# DE-010824_02.net
KiCad netlist of a schematic drawn in Altium Designer
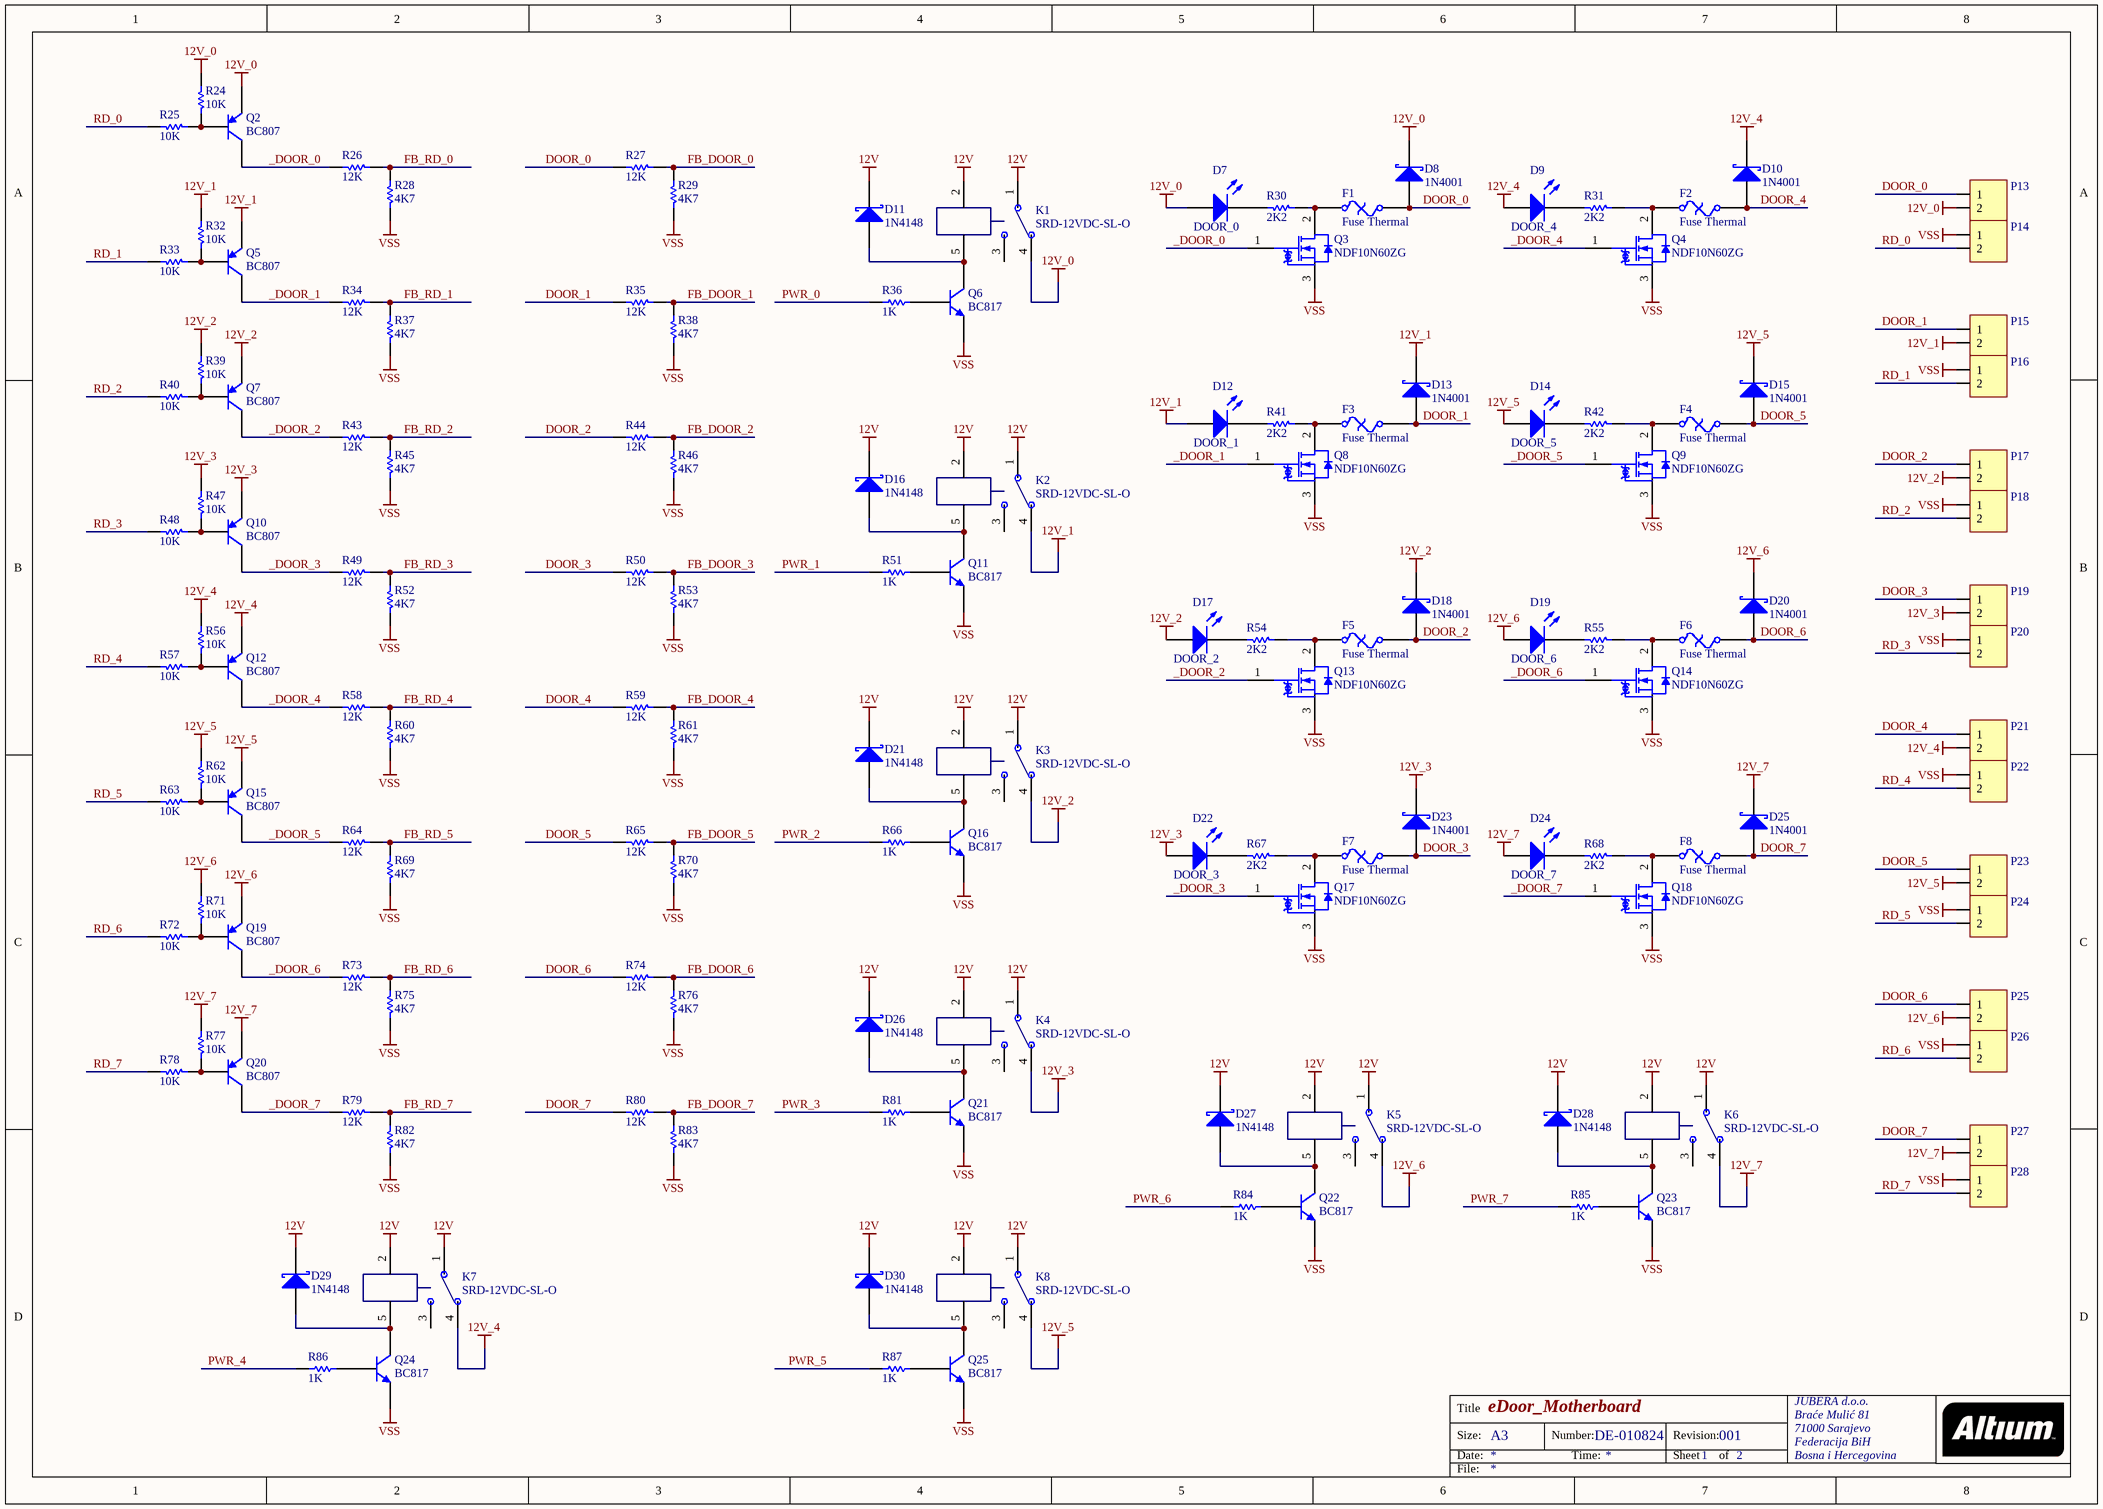
[diagram p0: DE-010824_02.SchDoc]

(export (version "E")
  (design (tool "Eeschema 10.0.6"))
  (components
    (comp (ref "D7")
      (value "DOOR_0")
      (footprint "1.6X0.8X0.8")
      (description "Blue Surface Mount Chip LED, Blue")
      (libsource (lib "DE-010824") (part "HSMB-C190"))
    )
    (comp (ref "D8")
      (value "1N4001")
      (footprint "SMB")
      (description "Schottky Diode")
      (libsource (lib "DE-010824") (part "D Schottky"))
    )
    (comp (ref "D9")
      (value "DOOR_4")
      (footprint "1.6X0.8X0.8")
      (description "Blue Surface Mount Chip LED, Blue")
      (libsource (lib "DE-010824") (part "HSMB-C190"))
    )
    (comp (ref "D10")
      (value "1N4001")
      (footprint "SMB")
      (description "Schottky Diode")
      (libsource (lib "DE-010824") (part "D Schottky"))
    )
    (comp (ref "D11")
      (value "1N4148")
      (footprint "SOD323")
      (description "Schottky Barrier Diode")
      (libsource (lib "DE-010824") (part "1PS76SB10"))
    )
    (comp (ref "D12")
      (value "DOOR_1")
      (footprint "1.6X0.8X0.8")
      (description "Blue Surface Mount Chip LED, Blue")
      (libsource (lib "DE-010824") (part "HSMB-C190"))
    )
    (comp (ref "D13")
      (value "1N4001")
      (footprint "SMB")
      (description "Schottky Diode")
      (libsource (lib "DE-010824") (part "D Schottky"))
    )
    (comp (ref "D14")
      (value "DOOR_5")
      (footprint "1.6X0.8X0.8")
      (description "Blue Surface Mount Chip LED, Blue")
      (libsource (lib "DE-010824") (part "HSMB-C190"))
    )
    (comp (ref "D15")
      (value "1N4001")
      (footprint "SMB")
      (description "Schottky Diode")
      (libsource (lib "DE-010824") (part "D Schottky"))
    )
    (comp (ref "D16")
      (value "1N4148")
      (footprint "SOD323")
      (description "Schottky Barrier Diode")
      (libsource (lib "DE-010824") (part "1PS76SB10"))
    )
    (comp (ref "D17")
      (value "DOOR_2")
      (footprint "1.6X0.8X0.8")
      (description "Blue Surface Mount Chip LED, Blue")
      (libsource (lib "DE-010824") (part "HSMB-C190"))
    )
    (comp (ref "D18")
      (value "1N4001")
      (footprint "SMB")
      (description "Schottky Diode")
      (libsource (lib "DE-010824") (part "D Schottky"))
    )
    (comp (ref "D19")
      (value "DOOR_6")
      (footprint "1.6X0.8X0.8")
      (description "Blue Surface Mount Chip LED, Blue")
      (libsource (lib "DE-010824") (part "HSMB-C190"))
    )
    (comp (ref "D20")
      (value "1N4001")
      (footprint "SMB")
      (description "Schottky Diode")
      (libsource (lib "DE-010824") (part "D Schottky"))
    )
    (comp (ref "D21")
      (value "1N4148")
      (footprint "SOD323")
      (description "Schottky Barrier Diode")
      (libsource (lib "DE-010824") (part "1PS76SB10"))
    )
    (comp (ref "D22")
      (value "DOOR_3")
      (footprint "1.6X0.8X0.8")
      (description "Blue Surface Mount Chip LED, Blue")
      (libsource (lib "DE-010824") (part "HSMB-C190"))
    )
    (comp (ref "D23")
      (value "1N4001")
      (footprint "SMB")
      (description "Schottky Diode")
      (libsource (lib "DE-010824") (part "D Schottky"))
    )
    (comp (ref "D24")
      (value "DOOR_7")
      (footprint "1.6X0.8X0.8")
      (description "Blue Surface Mount Chip LED, Blue")
      (libsource (lib "DE-010824") (part "HSMB-C190"))
    )
    (comp (ref "D25")
      (value "1N4001")
      (footprint "SMB")
      (description "Schottky Diode")
      (libsource (lib "DE-010824") (part "D Schottky"))
    )
    (comp (ref "D26")
      (value "1N4148")
      (footprint "SOD323")
      (description "Schottky Barrier Diode")
      (libsource (lib "DE-010824") (part "1PS76SB10"))
    )
    (comp (ref "D27")
      (value "1N4148")
      (footprint "SOD323")
      (description "Schottky Barrier Diode")
      (libsource (lib "DE-010824") (part "1PS76SB10"))
    )
    (comp (ref "D28")
      (value "1N4148")
      (footprint "SOD323")
      (description "Schottky Barrier Diode")
      (libsource (lib "DE-010824") (part "1PS76SB10"))
    )
    (comp (ref "D29")
      (value "1N4148")
      (footprint "SOD323")
      (description "Schottky Barrier Diode")
      (libsource (lib "DE-010824") (part "1PS76SB10"))
    )
    (comp (ref "D30")
      (value "1N4148")
      (footprint "SOD323")
      (description "Schottky Barrier Diode")
      (libsource (lib "DE-010824") (part "1PS76SB10"))
    )
    (comp (ref "F1")
      (value "Fuse Thermal")
      (footprint "PIN-W2/E2.8")
      (description "Thermal Fuse")
      (libsource (lib "Miscellaneous Devices") (part "Fuse Thermal"))
    )
    (comp (ref "F2")
      (value "Fuse Thermal")
      (footprint "PIN-W2/E2.8")
      (description "Thermal Fuse")
      (libsource (lib "Miscellaneous Devices") (part "Fuse Thermal"))
    )
    (comp (ref "F3")
      (value "Fuse Thermal")
      (footprint "PIN-W2/E2.8")
      (description "Thermal Fuse")
      (libsource (lib "Miscellaneous Devices") (part "Fuse Thermal"))
    )
    (comp (ref "F4")
      (value "Fuse Thermal")
      (footprint "PIN-W2/E2.8")
      (description "Thermal Fuse")
      (libsource (lib "Miscellaneous Devices") (part "Fuse Thermal"))
    )
    (comp (ref "F5")
      (value "Fuse Thermal")
      (footprint "PIN-W2/E2.8")
      (description "Thermal Fuse")
      (libsource (lib "Miscellaneous Devices") (part "Fuse Thermal"))
    )
    (comp (ref "F6")
      (value "Fuse Thermal")
      (footprint "PIN-W2/E2.8")
      (description "Thermal Fuse")
      (libsource (lib "Miscellaneous Devices") (part "Fuse Thermal"))
    )
    (comp (ref "F7")
      (value "Fuse Thermal")
      (footprint "PIN-W2/E2.8")
      (description "Thermal Fuse")
      (libsource (lib "Miscellaneous Devices") (part "Fuse Thermal"))
    )
    (comp (ref "F8")
      (value "Fuse Thermal")
      (footprint "PIN-W2/E2.8")
      (description "Thermal Fuse")
      (libsource (lib "Miscellaneous Devices") (part "Fuse Thermal"))
    )
    (comp (ref "K1")
      (value "SRD-12VDC-SL-O")
      (footprint "SRD-12VDC-SL-O")
      (description "SPDT PCB relay 12Vc coil")
      (libsource (lib "DE-010824") (part "SRD-12VDC-SL-O"))
    )
    (comp (ref "K2")
      (value "SRD-12VDC-SL-O")
      (footprint "SRD-12VDC-SL-O")
      (description "SPDT PCB relay 12Vc coil")
      (libsource (lib "DE-010824") (part "SRD-12VDC-SL-O"))
    )
    (comp (ref "K3")
      (value "SRD-12VDC-SL-O")
      (footprint "SRD-12VDC-SL-O")
      (description "SPDT PCB relay 12Vc coil")
      (libsource (lib "DE-010824") (part "SRD-12VDC-SL-O"))
    )
    (comp (ref "K4")
      (value "SRD-12VDC-SL-O")
      (footprint "SRD-12VDC-SL-O")
      (description "SPDT PCB relay 12Vc coil")
      (libsource (lib "DE-010824") (part "SRD-12VDC-SL-O"))
    )
    (comp (ref "K5")
      (value "SRD-12VDC-SL-O")
      (footprint "SRD-12VDC-SL-O")
      (description "SPDT PCB relay 12Vc coil")
      (libsource (lib "DE-010824") (part "SRD-12VDC-SL-O"))
    )
    (comp (ref "K6")
      (value "SRD-12VDC-SL-O")
      (footprint "SRD-12VDC-SL-O")
      (description "SPDT PCB relay 12Vc coil")
      (libsource (lib "DE-010824") (part "SRD-12VDC-SL-O"))
    )
    (comp (ref "K7")
      (value "SRD-12VDC-SL-O")
      (footprint "SRD-12VDC-SL-O")
      (description "SPDT PCB relay 12Vc coil")
      (libsource (lib "DE-010824") (part "SRD-12VDC-SL-O"))
    )
    (comp (ref "K8")
      (value "SRD-12VDC-SL-O")
      (footprint "SRD-12VDC-SL-O")
      (description "SPDT PCB relay 12Vc coil")
      (libsource (lib "DE-010824") (part "SRD-12VDC-SL-O"))
    )
    (comp (ref "P13")
      (value "DOOR_0")
      (footprint "TERMINAL BLOK 2")
      (description "Terminal blok konektor 3,5 mm")
      (libsource (lib "DE-010824") (part "TERMINAL BLOK 2"))
    )
    (comp (ref "P14")
      (value "GND")
      (footprint "TERMINAL BLOK 2")
      (description "Terminal blok konektor 3,5 mm")
      (libsource (lib "DE-010824") (part "TERMINAL BLOK 2"))
    )
    (comp (ref "P15")
      (value "DOOR_0")
      (footprint "TERMINAL BLOK 2")
      (description "Terminal blok konektor 3,5 mm")
      (libsource (lib "DE-010824") (part "TERMINAL BLOK 2"))
    )
    (comp (ref "P16")
      (value "GND")
      (footprint "TERMINAL BLOK 2")
      (description "Terminal blok konektor 3,5 mm")
      (libsource (lib "DE-010824") (part "TERMINAL BLOK 2"))
    )
    (comp (ref "P17")
      (value "DOOR_0")
      (footprint "TERMINAL BLOK 2")
      (description "Terminal blok konektor 3,5 mm")
      (libsource (lib "DE-010824") (part "TERMINAL BLOK 2"))
    )
    (comp (ref "P18")
      (value "GND")
      (footprint "TERMINAL BLOK 2")
      (description "Terminal blok konektor 3,5 mm")
      (libsource (lib "DE-010824") (part "TERMINAL BLOK 2"))
    )
    (comp (ref "P19")
      (value "DOOR_0")
      (footprint "TERMINAL BLOK 2")
      (description "Terminal blok konektor 3,5 mm")
      (libsource (lib "DE-010824") (part "TERMINAL BLOK 2"))
    )
    (comp (ref "P20")
      (value "GND")
      (footprint "TERMINAL BLOK 2")
      (description "Terminal blok konektor 3,5 mm")
      (libsource (lib "DE-010824") (part "TERMINAL BLOK 2"))
    )
    (comp (ref "P21")
      (value "DOOR_0")
      (footprint "TERMINAL BLOK 2")
      (description "Terminal blok konektor 3,5 mm")
      (libsource (lib "DE-010824") (part "TERMINAL BLOK 2"))
    )
    (comp (ref "P22")
      (value "GND")
      (footprint "TERMINAL BLOK 2")
      (description "Terminal blok konektor 3,5 mm")
      (libsource (lib "DE-010824") (part "TERMINAL BLOK 2"))
    )
    (comp (ref "P23")
      (value "DOOR_0")
      (footprint "TERMINAL BLOK 2")
      (description "Terminal blok konektor 3,5 mm")
      (libsource (lib "DE-010824") (part "TERMINAL BLOK 2"))
    )
    (comp (ref "P24")
      (value "GND")
      (footprint "TERMINAL BLOK 2")
      (description "Terminal blok konektor 3,5 mm")
      (libsource (lib "DE-010824") (part "TERMINAL BLOK 2"))
    )
    (comp (ref "P25")
      (value "DOOR_0")
      (footprint "TERMINAL BLOK 2")
      (description "Terminal blok konektor 3,5 mm")
      (libsource (lib "DE-010824") (part "TERMINAL BLOK 2"))
    )
    (comp (ref "P26")
      (value "GND")
      (footprint "TERMINAL BLOK 2")
      (description "Terminal blok konektor 3,5 mm")
      (libsource (lib "DE-010824") (part "TERMINAL BLOK 2"))
    )
    (comp (ref "P27")
      (value "DOOR_0")
      (footprint "TERMINAL BLOK 2")
      (description "Terminal blok konektor 3,5 mm")
      (libsource (lib "DE-010824") (part "TERMINAL BLOK 2"))
    )
    (comp (ref "P28")
      (value "GND")
      (footprint "TERMINAL BLOK 2")
      (description "Terminal blok konektor 3,5 mm")
      (libsource (lib "DE-010824") (part "TERMINAL BLOK 2"))
    )
    (comp (ref "Q2")
      (value "BC807")
      (footprint "SOT23_N")
      (description "PNP General-purpose Transistor")
      (libsource (lib "DE-010824") (part "BC807"))
    )
    (comp (ref "Q3")
      (value "NDF10N60ZG")
      (footprint "ONSC-TO-220-3-221D-03")
      (description "N-Channel Power MOSFET 600 V, 0.75 Ohm, 3-Pin TO-220, Pb-Free, Tube")
      (fields (field (name "MANUFACTURER") "On Semiconductor"))
      (libsource (lib "ON Semi MOSFETs") (part "NDF10N60ZG"))
    )
    (comp (ref "Q4")
      (value "NDF10N60ZG")
      (footprint "ONSC-TO-220-3-221D-03")
      (description "N-Channel Power MOSFET 600 V, 0.75 Ohm, 3-Pin TO-220, Pb-Free, Tube")
      (fields (field (name "MANUFACTURER") "On Semiconductor"))
      (libsource (lib "ON Semi MOSFETs") (part "NDF10N60ZG"))
    )
    (comp (ref "Q5")
      (value "BC807")
      (footprint "SOT23_N")
      (description "PNP General-purpose Transistor")
      (libsource (lib "DE-010824") (part "BC807"))
    )
    (comp (ref "Q6")
      (value "BC817")
      (footprint "SOT23_N")
      (description "NPN General-purpose Transistor")
      (libsource (lib "DE-010824") (part "BC817"))
    )
    (comp (ref "Q7")
      (value "BC807")
      (footprint "SOT23_N")
      (description "PNP General-purpose Transistor")
      (libsource (lib "DE-010824") (part "BC807"))
    )
    (comp (ref "Q8")
      (value "NDF10N60ZG")
      (footprint "ONSC-TO-220-3-221D-03")
      (description "N-Channel Power MOSFET 600 V, 0.75 Ohm, 3-Pin TO-220, Pb-Free, Tube")
      (fields (field (name "MANUFACTURER") "On Semiconductor"))
      (libsource (lib "ON Semi MOSFETs") (part "NDF10N60ZG"))
    )
    (comp (ref "Q9")
      (value "NDF10N60ZG")
      (footprint "ONSC-TO-220-3-221D-03")
      (description "N-Channel Power MOSFET 600 V, 0.75 Ohm, 3-Pin TO-220, Pb-Free, Tube")
      (fields (field (name "MANUFACTURER") "On Semiconductor"))
      (libsource (lib "ON Semi MOSFETs") (part "NDF10N60ZG"))
    )
    (comp (ref "Q10")
      (value "BC807")
      (footprint "SOT23_N")
      (description "PNP General-purpose Transistor")
      (libsource (lib "DE-010824") (part "BC807"))
    )
    (comp (ref "Q11")
      (value "BC817")
      (footprint "SOT23_N")
      (description "NPN General-purpose Transistor")
      (libsource (lib "DE-010824") (part "BC817"))
    )
    (comp (ref "Q12")
      (value "BC807")
      (footprint "SOT23_N")
      (description "PNP General-purpose Transistor")
      (libsource (lib "DE-010824") (part "BC807"))
    )
    (comp (ref "Q13")
      (value "NDF10N60ZG")
      (footprint "ONSC-TO-220-3-221D-03")
      (description "N-Channel Power MOSFET 600 V, 0.75 Ohm, 3-Pin TO-220, Pb-Free, Tube")
      (fields (field (name "MANUFACTURER") "On Semiconductor"))
      (libsource (lib "ON Semi MOSFETs") (part "NDF10N60ZG"))
    )
    (comp (ref "Q14")
      (value "NDF10N60ZG")
      (footprint "ONSC-TO-220-3-221D-03")
      (description "N-Channel Power MOSFET 600 V, 0.75 Ohm, 3-Pin TO-220, Pb-Free, Tube")
      (fields (field (name "MANUFACTURER") "On Semiconductor"))
      (libsource (lib "ON Semi MOSFETs") (part "NDF10N60ZG"))
    )
    (comp (ref "Q15")
      (value "BC807")
      (footprint "SOT23_N")
      (description "PNP General-purpose Transistor")
      (libsource (lib "DE-010824") (part "BC807"))
    )
    (comp (ref "Q16")
      (value "BC817")
      (footprint "SOT23_N")
      (description "NPN General-purpose Transistor")
      (libsource (lib "DE-010824") (part "BC817"))
    )
    (comp (ref "Q17")
      (value "NDF10N60ZG")
      (footprint "ONSC-TO-220-3-221D-03")
      (description "N-Channel Power MOSFET 600 V, 0.75 Ohm, 3-Pin TO-220, Pb-Free, Tube")
      (fields (field (name "MANUFACTURER") "On Semiconductor"))
      (libsource (lib "ON Semi MOSFETs") (part "NDF10N60ZG"))
    )
    (comp (ref "Q18")
      (value "NDF10N60ZG")
      (footprint "ONSC-TO-220-3-221D-03")
      (description "N-Channel Power MOSFET 600 V, 0.75 Ohm, 3-Pin TO-220, Pb-Free, Tube")
      (fields (field (name "MANUFACTURER") "On Semiconductor"))
      (libsource (lib "ON Semi MOSFETs") (part "NDF10N60ZG"))
    )
    (comp (ref "Q19")
      (value "BC807")
      (footprint "SOT23_N")
      (description "PNP General-purpose Transistor")
      (libsource (lib "DE-010824") (part "BC807"))
    )
    (comp (ref "Q20")
      (value "BC807")
      (footprint "SOT23_N")
      (description "PNP General-purpose Transistor")
      (libsource (lib "DE-010824") (part "BC807"))
    )
    (comp (ref "Q21")
      (value "BC817")
      (footprint "SOT23_N")
      (description "NPN General-purpose Transistor")
      (libsource (lib "DE-010824") (part "BC817"))
    )
    (comp (ref "Q22")
      (value "BC817")
      (footprint "SOT23_N")
      (description "NPN General-purpose Transistor")
      (libsource (lib "DE-010824") (part "BC817"))
    )
    (comp (ref "Q23")
      (value "BC817")
      (footprint "SOT23_N")
      (description "NPN General-purpose Transistor")
      (libsource (lib "DE-010824") (part "BC817"))
    )
    (comp (ref "Q24")
      (value "BC817")
      (footprint "SOT23_N")
      (description "NPN General-purpose Transistor")
      (libsource (lib "DE-010824") (part "BC817"))
    )
    (comp (ref "Q25")
      (value "BC817")
      (footprint "SOT23_N")
      (description "NPN General-purpose Transistor")
      (libsource (lib "DE-010824") (part "BC817"))
    )
    (comp (ref "R24") (value "10K") (footprint "ERA-0603") (libsource (lib "DE-220817") (part "ERAV")))
    (comp (ref "R25") (value "10K") (footprint "ERA-0603") (libsource (lib "DE-220817") (part "ERAV")))
    (comp (ref "R26") (value "12K") (footprint "ERA-0603") (libsource (lib "DE-220817") (part "ERAV")))
    (comp (ref "R27") (value "12K") (footprint "ERA-0603") (libsource (lib "DE-220817") (part "ERAV")))
    (comp (ref "R28") (value "4K7") (footprint "ERA-0603") (libsource (lib "DE-220817") (part "ERAV")))
    (comp (ref "R29") (value "4K7") (footprint "ERA-0603") (libsource (lib "DE-220817") (part "ERAV")))
    (comp (ref "R30") (value "2K2") (footprint "ERA-0603") (libsource (lib "DE-220817") (part "ERAV")))
    (comp (ref "R31") (value "2K2") (footprint "ERA-0603") (libsource (lib "DE-220817") (part "ERAV")))
    (comp (ref "R32") (value "10K") (footprint "ERA-0603") (libsource (lib "DE-220817") (part "ERAV")))
    (comp (ref "R33") (value "10K") (footprint "ERA-0603") (libsource (lib "DE-220817") (part "ERAV")))
    (comp (ref "R34") (value "12K") (footprint "ERA-0603") (libsource (lib "DE-220817") (part "ERAV")))
    (comp (ref "R35") (value "12K") (footprint "ERA-0603") (libsource (lib "DE-220817") (part "ERAV")))
    (comp (ref "R36") (value "1K") (footprint "ERA-0603") (libsource (lib "DE-220817") (part "ERAV")))
    (comp (ref "R37") (value "4K7") (footprint "ERA-0603") (libsource (lib "DE-220817") (part "ERAV")))
    (comp (ref "R38") (value "4K7") (footprint "ERA-0603") (libsource (lib "DE-220817") (part "ERAV")))
    (comp (ref "R39") (value "10K") (footprint "ERA-0603") (libsource (lib "DE-220817") (part "ERAV")))
    (comp (ref "R40") (value "10K") (footprint "ERA-0603") (libsource (lib "DE-220817") (part "ERAV")))
    (comp (ref "R41") (value "2K2") (footprint "ERA-0603") (libsource (lib "DE-220817") (part "ERAV")))
    (comp (ref "R42") (value "2K2") (footprint "ERA-0603") (libsource (lib "DE-220817") (part "ERAV")))
    (comp (ref "R43") (value "12K") (footprint "ERA-0603") (libsource (lib "DE-220817") (part "ERAV")))
    (comp (ref "R44") (value "12K") (footprint "ERA-0603") (libsource (lib "DE-220817") (part "ERAV")))
    (comp (ref "R45") (value "4K7") (footprint "ERA-0603") (libsource (lib "DE-220817") (part "ERAV")))
    (comp (ref "R46") (value "4K7") (footprint "ERA-0603") (libsource (lib "DE-220817") (part "ERAV")))
    (comp (ref "R47") (value "10K") (footprint "ERA-0603") (libsource (lib "DE-220817") (part "ERAV")))
    (comp (ref "R48") (value "10K") (footprint "ERA-0603") (libsource (lib "DE-220817") (part "ERAV")))
    (comp (ref "R49") (value "12K") (footprint "ERA-0603") (libsource (lib "DE-220817") (part "ERAV")))
    (comp (ref "R50") (value "12K") (footprint "ERA-0603") (libsource (lib "DE-220817") (part "ERAV")))
    (comp (ref "R51") (value "1K") (footprint "ERA-0603") (libsource (lib "DE-220817") (part "ERAV")))
    (comp (ref "R52") (value "4K7") (footprint "ERA-0603") (libsource (lib "DE-220817") (part "ERAV")))
    (comp (ref "R53") (value "4K7") (footprint "ERA-0603") (libsource (lib "DE-220817") (part "ERAV")))
    (comp (ref "R54") (value "2K2") (footprint "ERA-0603") (libsource (lib "DE-220817") (part "ERAV")))
    (comp (ref "R55") (value "2K2") (footprint "ERA-0603") (libsource (lib "DE-220817") (part "ERAV")))
    (comp (ref "R56") (value "10K") (footprint "ERA-0603") (libsource (lib "DE-220817") (part "ERAV")))
    (comp (ref "R57") (value "10K") (footprint "ERA-0603") (libsource (lib "DE-220817") (part "ERAV")))
    (comp (ref "R58") (value "12K") (footprint "ERA-0603") (libsource (lib "DE-220817") (part "ERAV")))
    (comp (ref "R59") (value "12K") (footprint "ERA-0603") (libsource (lib "DE-220817") (part "ERAV")))
    (comp (ref "R60") (value "4K7") (footprint "ERA-0603") (libsource (lib "DE-220817") (part "ERAV")))
    (comp (ref "R61") (value "4K7") (footprint "ERA-0603") (libsource (lib "DE-220817") (part "ERAV")))
    (comp (ref "R62") (value "10K") (footprint "ERA-0603") (libsource (lib "DE-220817") (part "ERAV")))
    (comp (ref "R63") (value "10K") (footprint "ERA-0603") (libsource (lib "DE-220817") (part "ERAV")))
    (comp (ref "R64") (value "12K") (footprint "ERA-0603") (libsource (lib "DE-220817") (part "ERAV")))
    (comp (ref "R65") (value "12K") (footprint "ERA-0603") (libsource (lib "DE-220817") (part "ERAV")))
    (comp (ref "R66") (value "1K") (footprint "ERA-0603") (libsource (lib "DE-220817") (part "ERAV")))
    (comp (ref "R67") (value "2K2") (footprint "ERA-0603") (libsource (lib "DE-220817") (part "ERAV")))
    (comp (ref "R68") (value "2K2") (footprint "ERA-0603") (libsource (lib "DE-220817") (part "ERAV")))
    (comp (ref "R69") (value "4K7") (footprint "ERA-0603") (libsource (lib "DE-220817") (part "ERAV")))
    (comp (ref "R70") (value "4K7") (footprint "ERA-0603") (libsource (lib "DE-220817") (part "ERAV")))
    (comp (ref "R71") (value "10K") (footprint "ERA-0603") (libsource (lib "DE-220817") (part "ERAV")))
    (comp (ref "R72") (value "10K") (footprint "ERA-0603") (libsource (lib "DE-220817") (part "ERAV")))
    (comp (ref "R73") (value "12K") (footprint "ERA-0603") (libsource (lib "DE-220817") (part "ERAV")))
    (comp (ref "R74") (value "12K") (footprint "ERA-0603") (libsource (lib "DE-220817") (part "ERAV")))
    (comp (ref "R75") (value "4K7") (footprint "ERA-0603") (libsource (lib "DE-220817") (part "ERAV")))
    (comp (ref "R76") (value "4K7") (footprint "ERA-0603") (libsource (lib "DE-220817") (part "ERAV")))
    (comp (ref "R77") (value "10K") (footprint "ERA-0603") (libsource (lib "DE-220817") (part "ERAV")))
    (comp (ref "R78") (value "10K") (footprint "ERA-0603") (libsource (lib "DE-220817") (part "ERAV")))
    (comp (ref "R79") (value "12K") (footprint "ERA-0603") (libsource (lib "DE-220817") (part "ERAV")))
    (comp (ref "R80") (value "12K") (footprint "ERA-0603") (libsource (lib "DE-220817") (part "ERAV")))
    (comp (ref "R81") (value "1K") (footprint "ERA-0603") (libsource (lib "DE-220817") (part "ERAV")))
    (comp (ref "R82") (value "4K7") (footprint "ERA-0603") (libsource (lib "DE-220817") (part "ERAV")))
    (comp (ref "R83") (value "4K7") (footprint "ERA-0603") (libsource (lib "DE-220817") (part "ERAV")))
    (comp (ref "R84") (value "1K") (footprint "ERA-0603") (libsource (lib "DE-220817") (part "ERAV")))
    (comp (ref "R85") (value "1K") (footprint "ERA-0603") (libsource (lib "DE-220817") (part "ERAV")))
    (comp (ref "R86") (value "1K") (footprint "ERA-0603") (libsource (lib "DE-220817") (part "ERAV")))
    (comp (ref "R87") (value "1K") (footprint "ERA-0603") (libsource (lib "DE-220817") (part "ERAV")))
  )
  (nets
    (net (code "1") (name "/DOOR_0") (class "Default")
      (node (ref "D8") (pin "1") (pinfunction "A_1") (pintype "passive"))
      (node (ref "F1") (pin "2") (pinfunction "2_2") (pintype "passive"))
      (node (ref "P13") (pin "1") (pinfunction "1_1") (pintype "passive"))
      (node (ref "R27") (pin "1") (pinfunction "1_1") (pintype "passive"))
    )
    (net (code "2") (name "/DOOR_1") (class "Default")
      (node (ref "D13") (pin "1") (pinfunction "A_1") (pintype "passive"))
      (node (ref "F3") (pin "2") (pinfunction "2_2") (pintype "passive"))
      (node (ref "P15") (pin "1") (pinfunction "1_1") (pintype "passive"))
      (node (ref "R35") (pin "1") (pinfunction "1_1") (pintype "passive"))
    )
    (net (code "3") (name "/DOOR_2") (class "Default")
      (node (ref "D18") (pin "1") (pinfunction "A_1") (pintype "passive"))
      (node (ref "F5") (pin "2") (pinfunction "2_2") (pintype "passive"))
      (node (ref "P17") (pin "1") (pinfunction "1_1") (pintype "passive"))
      (node (ref "R44") (pin "1") (pinfunction "1_1") (pintype "passive"))
    )
    (net (code "4") (name "/DOOR_3") (class "Default")
      (node (ref "D23") (pin "1") (pinfunction "A_1") (pintype "passive"))
      (node (ref "F7") (pin "2") (pinfunction "2_2") (pintype "passive"))
      (node (ref "P19") (pin "1") (pinfunction "1_1") (pintype "passive"))
      (node (ref "R50") (pin "1") (pinfunction "1_1") (pintype "passive"))
    )
    (net (code "5") (name "/DOOR_4") (class "Default")
      (node (ref "D10") (pin "1") (pinfunction "A_1") (pintype "passive"))
      (node (ref "F2") (pin "2") (pinfunction "2_2") (pintype "passive"))
      (node (ref "P21") (pin "1") (pinfunction "1_1") (pintype "passive"))
      (node (ref "R59") (pin "1") (pinfunction "1_1") (pintype "passive"))
    )
    (net (code "6") (name "/DOOR_5") (class "Default")
      (node (ref "D15") (pin "1") (pinfunction "A_1") (pintype "passive"))
      (node (ref "F4") (pin "2") (pinfunction "2_2") (pintype "passive"))
      (node (ref "P23") (pin "1") (pinfunction "1_1") (pintype "passive"))
      (node (ref "R65") (pin "1") (pinfunction "1_1") (pintype "passive"))
    )
    (net (code "7") (name "/DOOR_6") (class "Default")
      (node (ref "D20") (pin "1") (pinfunction "A_1") (pintype "passive"))
      (node (ref "F6") (pin "2") (pinfunction "2_2") (pintype "passive"))
      (node (ref "P25") (pin "1") (pinfunction "1_1") (pintype "passive"))
      (node (ref "R74") (pin "1") (pinfunction "1_1") (pintype "passive"))
    )
    (net (code "8") (name "/DOOR_7") (class "Default")
      (node (ref "D25") (pin "1") (pinfunction "A_1") (pintype "passive"))
      (node (ref "F8") (pin "2") (pinfunction "2_2") (pintype "passive"))
      (node (ref "P27") (pin "1") (pinfunction "1_1") (pintype "passive"))
      (node (ref "R80") (pin "1") (pinfunction "1_1") (pintype "passive"))
    )
    (net (code "9") (name "/FB_DOOR_0") (class "Default")
      (node (ref "R27") (pin "2") (pinfunction "2_2") (pintype "passive"))
      (node (ref "R29") (pin "2") (pinfunction "2_2") (pintype "passive"))
    )
    (net (code "10") (name "/FB_DOOR_1") (class "Default")
      (node (ref "R35") (pin "2") (pinfunction "2_2") (pintype "passive"))
      (node (ref "R38") (pin "2") (pinfunction "2_2") (pintype "passive"))
    )
    (net (code "11") (name "/FB_DOOR_2") (class "Default")
      (node (ref "R44") (pin "2") (pinfunction "2_2") (pintype "passive"))
      (node (ref "R46") (pin "2") (pinfunction "2_2") (pintype "passive"))
    )
    (net (code "12") (name "/FB_DOOR_3") (class "Default")
      (node (ref "R50") (pin "2") (pinfunction "2_2") (pintype "passive"))
      (node (ref "R53") (pin "2") (pinfunction "2_2") (pintype "passive"))
    )
    (net (code "13") (name "/FB_DOOR_4") (class "Default")
      (node (ref "R59") (pin "2") (pinfunction "2_2") (pintype "passive"))
      (node (ref "R61") (pin "2") (pinfunction "2_2") (pintype "passive"))
    )
    (net (code "14") (name "/FB_DOOR_5") (class "Default")
      (node (ref "R65") (pin "2") (pinfunction "2_2") (pintype "passive"))
      (node (ref "R70") (pin "2") (pinfunction "2_2") (pintype "passive"))
    )
    (net (code "15") (name "/FB_DOOR_6") (class "Default")
      (node (ref "R74") (pin "2") (pinfunction "2_2") (pintype "passive"))
      (node (ref "R76") (pin "2") (pinfunction "2_2") (pintype "passive"))
    )
    (net (code "16") (name "/FB_DOOR_7") (class "Default")
      (node (ref "R80") (pin "2") (pinfunction "2_2") (pintype "passive"))
      (node (ref "R83") (pin "2") (pinfunction "2_2") (pintype "passive"))
    )
    (net (code "17") (name "/FB_RD_0") (class "Default")
      (node (ref "R26") (pin "2") (pinfunction "2_2") (pintype "passive"))
      (node (ref "R28") (pin "2") (pinfunction "2_2") (pintype "passive"))
    )
    (net (code "18") (name "/FB_RD_1") (class "Default")
      (node (ref "R34") (pin "2") (pinfunction "2_2") (pintype "passive"))
      (node (ref "R37") (pin "2") (pinfunction "2_2") (pintype "passive"))
    )
    (net (code "19") (name "/FB_RD_2") (class "Default")
      (node (ref "R43") (pin "2") (pinfunction "2_2") (pintype "passive"))
      (node (ref "R45") (pin "2") (pinfunction "2_2") (pintype "passive"))
    )
    (net (code "20") (name "/FB_RD_3") (class "Default")
      (node (ref "R49") (pin "2") (pinfunction "2_2") (pintype "passive"))
      (node (ref "R52") (pin "2") (pinfunction "2_2") (pintype "passive"))
    )
    (net (code "21") (name "/FB_RD_4") (class "Default")
      (node (ref "R58") (pin "2") (pinfunction "2_2") (pintype "passive"))
      (node (ref "R60") (pin "2") (pinfunction "2_2") (pintype "passive"))
    )
    (net (code "22") (name "/FB_RD_5") (class "Default")
      (node (ref "R64") (pin "2") (pinfunction "2_2") (pintype "passive"))
      (node (ref "R69") (pin "2") (pinfunction "2_2") (pintype "passive"))
    )
    (net (code "23") (name "/FB_RD_6") (class "Default")
      (node (ref "R73") (pin "2") (pinfunction "2_2") (pintype "passive"))
      (node (ref "R75") (pin "2") (pinfunction "2_2") (pintype "passive"))
    )
    (net (code "24") (name "/FB_RD_7") (class "Default")
      (node (ref "R79") (pin "2") (pinfunction "2_2") (pintype "passive"))
      (node (ref "R82") (pin "2") (pinfunction "2_2") (pintype "passive"))
    )
    (net (code "25") (name "/PWR_0") (class "Default")
      (node (ref "R36") (pin "2") (pinfunction "2_2") (pintype "passive"))
    )
    (net (code "26") (name "/PWR_1") (class "Default")
      (node (ref "R51") (pin "2") (pinfunction "2_2") (pintype "passive"))
    )
    (net (code "27") (name "/PWR_2") (class "Default")
      (node (ref "R66") (pin "2") (pinfunction "2_2") (pintype "passive"))
    )
    (net (code "28") (name "/PWR_3") (class "Default")
      (node (ref "R81") (pin "2") (pinfunction "2_2") (pintype "passive"))
    )
    (net (code "29") (name "/PWR_4") (class "Default")
      (node (ref "R86") (pin "2") (pinfunction "2_2") (pintype "passive"))
    )
    (net (code "30") (name "/PWR_5") (class "Default")
      (node (ref "R87") (pin "2") (pinfunction "2_2") (pintype "passive"))
    )
    (net (code "31") (name "/PWR_6") (class "Default")
      (node (ref "R84") (pin "2") (pinfunction "2_2") (pintype "passive"))
    )
    (net (code "32") (name "/PWR_7") (class "Default")
      (node (ref "R85") (pin "2") (pinfunction "2_2") (pintype "passive"))
    )
    (net (code "33") (name "/RD_0") (class "Default")
      (node (ref "P14") (pin "2") (pinfunction "2_2") (pintype "passive"))
      (node (ref "R25") (pin "1") (pinfunction "1_1") (pintype "passive"))
    )
    (net (code "34") (name "/RD_1") (class "Default")
      (node (ref "P16") (pin "2") (pinfunction "2_2") (pintype "passive"))
      (node (ref "R33") (pin "1") (pinfunction "1_1") (pintype "passive"))
    )
    (net (code "35") (name "/RD_2") (class "Default")
      (node (ref "P18") (pin "2") (pinfunction "2_2") (pintype "passive"))
      (node (ref "R40") (pin "1") (pinfunction "1_1") (pintype "passive"))
    )
    (net (code "36") (name "/RD_3") (class "Default")
      (node (ref "P20") (pin "2") (pinfunction "2_2") (pintype "passive"))
      (node (ref "R48") (pin "1") (pinfunction "1_1") (pintype "passive"))
    )
    (net (code "37") (name "/RD_4") (class "Default")
      (node (ref "P22") (pin "2") (pinfunction "2_2") (pintype "passive"))
      (node (ref "R57") (pin "1") (pinfunction "1_1") (pintype "passive"))
    )
    (net (code "38") (name "/RD_5") (class "Default")
      (node (ref "P24") (pin "2") (pinfunction "2_2") (pintype "passive"))
      (node (ref "R63") (pin "1") (pinfunction "1_1") (pintype "passive"))
    )
    (net (code "39") (name "/RD_6") (class "Default")
      (node (ref "P26") (pin "2") (pinfunction "2_2") (pintype "passive"))
      (node (ref "R72") (pin "1") (pinfunction "1_1") (pintype "passive"))
    )
    (net (code "40") (name "/RD_7") (class "Default")
      (node (ref "P28") (pin "2") (pinfunction "2_2") (pintype "passive"))
      (node (ref "R78") (pin "1") (pinfunction "1_1") (pintype "passive"))
    )
    (net (code "41") (name "/_DOOR_0") (class "Default")
      (node (ref "Q2") (pin "3") (pinfunction "C_3") (pintype "passive"))
      (node (ref "Q3") (pin "1") (pinfunction "G_1") (pintype "passive"))
      (node (ref "R26") (pin "1") (pinfunction "1_1") (pintype "passive"))
    )
    (net (code "42") (name "/_DOOR_1") (class "Default")
      (node (ref "Q5") (pin "3") (pinfunction "C_3") (pintype "passive"))
      (node (ref "Q8") (pin "1") (pinfunction "G_1") (pintype "passive"))
      (node (ref "R34") (pin "1") (pinfunction "1_1") (pintype "passive"))
    )
    (net (code "43") (name "/_DOOR_2") (class "Default")
      (node (ref "Q13") (pin "1") (pinfunction "G_1") (pintype "passive"))
      (node (ref "Q7") (pin "3") (pinfunction "C_3") (pintype "passive"))
      (node (ref "R43") (pin "1") (pinfunction "1_1") (pintype "passive"))
    )
    (net (code "44") (name "/_DOOR_3") (class "Default")
      (node (ref "Q10") (pin "3") (pinfunction "C_3") (pintype "passive"))
      (node (ref "Q17") (pin "1") (pinfunction "G_1") (pintype "passive"))
      (node (ref "R49") (pin "1") (pinfunction "1_1") (pintype "passive"))
    )
    (net (code "45") (name "/_DOOR_4") (class "Default")
      (node (ref "Q12") (pin "3") (pinfunction "C_3") (pintype "passive"))
      (node (ref "Q4") (pin "1") (pinfunction "G_1") (pintype "passive"))
      (node (ref "R58") (pin "1") (pinfunction "1_1") (pintype "passive"))
    )
    (net (code "46") (name "/_DOOR_5") (class "Default")
      (node (ref "Q15") (pin "3") (pinfunction "C_3") (pintype "passive"))
      (node (ref "Q9") (pin "1") (pinfunction "G_1") (pintype "passive"))
      (node (ref "R64") (pin "1") (pinfunction "1_1") (pintype "passive"))
    )
    (net (code "47") (name "/_DOOR_6") (class "Default")
      (node (ref "Q14") (pin "1") (pinfunction "G_1") (pintype "passive"))
      (node (ref "Q19") (pin "3") (pinfunction "C_3") (pintype "passive"))
      (node (ref "R73") (pin "1") (pinfunction "1_1") (pintype "passive"))
    )
    (net (code "48") (name "/_DOOR_7") (class "Default")
      (node (ref "Q18") (pin "1") (pinfunction "G_1") (pintype "passive"))
      (node (ref "Q20") (pin "3") (pinfunction "C_3") (pintype "passive"))
      (node (ref "R79") (pin "1") (pinfunction "1_1") (pintype "passive"))
    )
    (net (code "49") (name "12V") (class "Default")
      (node (ref "D11") (pin "1") (pinfunction "K_1") (pintype "passive"))
      (node (ref "D16") (pin "1") (pinfunction "K_1") (pintype "passive"))
      (node (ref "D21") (pin "1") (pinfunction "K_1") (pintype "passive"))
      (node (ref "D26") (pin "1") (pinfunction "K_1") (pintype "passive"))
      (node (ref "D27") (pin "1") (pinfunction "K_1") (pintype "passive"))
      (node (ref "D28") (pin "1") (pinfunction "K_1") (pintype "passive"))
      (node (ref "D29") (pin "1") (pinfunction "K_1") (pintype "passive"))
      (node (ref "D30") (pin "1") (pinfunction "K_1") (pintype "passive"))
      (node (ref "K1") (pin "1") (pinfunction "1_1") (pintype "passive"))
      (node (ref "K1") (pin "2") (pinfunction "2_2") (pintype "passive"))
      (node (ref "K2") (pin "1") (pinfunction "1_1") (pintype "passive"))
      (node (ref "K2") (pin "2") (pinfunction "2_2") (pintype "passive"))
      (node (ref "K3") (pin "1") (pinfunction "1_1") (pintype "passive"))
      (node (ref "K3") (pin "2") (pinfunction "2_2") (pintype "passive"))
      (node (ref "K4") (pin "1") (pinfunction "1_1") (pintype "passive"))
      (node (ref "K4") (pin "2") (pinfunction "2_2") (pintype "passive"))
      (node (ref "K5") (pin "1") (pinfunction "1_1") (pintype "passive"))
      (node (ref "K5") (pin "2") (pinfunction "2_2") (pintype "passive"))
      (node (ref "K6") (pin "1") (pinfunction "1_1") (pintype "passive"))
      (node (ref "K6") (pin "2") (pinfunction "2_2") (pintype "passive"))
      (node (ref "K7") (pin "1") (pinfunction "1_1") (pintype "passive"))
      (node (ref "K7") (pin "2") (pinfunction "2_2") (pintype "passive"))
      (node (ref "K8") (pin "1") (pinfunction "1_1") (pintype "passive"))
      (node (ref "K8") (pin "2") (pinfunction "2_2") (pintype "passive"))
    )
    (net (code "50") (name "12V_0") (class "Default")
      (node (ref "D7") (pin "1") (pinfunction "A_1") (pintype "passive"))
      (node (ref "D8") (pin "2") (pinfunction "K_2") (pintype "passive"))
      (node (ref "K1") (pin "4") (pinfunction "4_4") (pintype "passive"))
      (node (ref "P13") (pin "2") (pinfunction "2_2") (pintype "passive"))
      (node (ref "Q2") (pin "2") (pinfunction "E_2") (pintype "passive"))
      (node (ref "R24") (pin "2") (pinfunction "2_2") (pintype "passive"))
    )
    (net (code "51") (name "12V_1") (class "Default")
      (node (ref "D12") (pin "1") (pinfunction "A_1") (pintype "passive"))
      (node (ref "D13") (pin "2") (pinfunction "K_2") (pintype "passive"))
      (node (ref "K2") (pin "4") (pinfunction "4_4") (pintype "passive"))
      (node (ref "P15") (pin "2") (pinfunction "2_2") (pintype "passive"))
      (node (ref "Q5") (pin "2") (pinfunction "E_2") (pintype "passive"))
      (node (ref "R32") (pin "2") (pinfunction "2_2") (pintype "passive"))
    )
    (net (code "52") (name "12V_2") (class "Default")
      (node (ref "D17") (pin "1") (pinfunction "A_1") (pintype "passive"))
      (node (ref "D18") (pin "2") (pinfunction "K_2") (pintype "passive"))
      (node (ref "K3") (pin "4") (pinfunction "4_4") (pintype "passive"))
      (node (ref "P17") (pin "2") (pinfunction "2_2") (pintype "passive"))
      (node (ref "Q7") (pin "2") (pinfunction "E_2") (pintype "passive"))
      (node (ref "R39") (pin "2") (pinfunction "2_2") (pintype "passive"))
    )
    (net (code "53") (name "12V_3") (class "Default")
      (node (ref "D22") (pin "1") (pinfunction "A_1") (pintype "passive"))
      (node (ref "D23") (pin "2") (pinfunction "K_2") (pintype "passive"))
      (node (ref "K4") (pin "4") (pinfunction "4_4") (pintype "passive"))
      (node (ref "P19") (pin "2") (pinfunction "2_2") (pintype "passive"))
      (node (ref "Q10") (pin "2") (pinfunction "E_2") (pintype "passive"))
      (node (ref "R47") (pin "2") (pinfunction "2_2") (pintype "passive"))
    )
    (net (code "54") (name "12V_4") (class "Default")
      (node (ref "D10") (pin "2") (pinfunction "K_2") (pintype "passive"))
      (node (ref "D9") (pin "1") (pinfunction "A_1") (pintype "passive"))
      (node (ref "K7") (pin "4") (pinfunction "4_4") (pintype "passive"))
      (node (ref "P21") (pin "2") (pinfunction "2_2") (pintype "passive"))
      (node (ref "Q12") (pin "2") (pinfunction "E_2") (pintype "passive"))
      (node (ref "R56") (pin "2") (pinfunction "2_2") (pintype "passive"))
    )
    (net (code "55") (name "12V_5") (class "Default")
      (node (ref "D14") (pin "1") (pinfunction "A_1") (pintype "passive"))
      (node (ref "D15") (pin "2") (pinfunction "K_2") (pintype "passive"))
      (node (ref "K8") (pin "4") (pinfunction "4_4") (pintype "passive"))
      (node (ref "P23") (pin "2") (pinfunction "2_2") (pintype "passive"))
      (node (ref "Q15") (pin "2") (pinfunction "E_2") (pintype "passive"))
      (node (ref "R62") (pin "2") (pinfunction "2_2") (pintype "passive"))
    )
    (net (code "56") (name "12V_6") (class "Default")
      (node (ref "D19") (pin "1") (pinfunction "A_1") (pintype "passive"))
      (node (ref "D20") (pin "2") (pinfunction "K_2") (pintype "passive"))
      (node (ref "K5") (pin "4") (pinfunction "4_4") (pintype "passive"))
      (node (ref "P25") (pin "2") (pinfunction "2_2") (pintype "passive"))
      (node (ref "Q19") (pin "2") (pinfunction "E_2") (pintype "passive"))
      (node (ref "R71") (pin "2") (pinfunction "2_2") (pintype "passive"))
    )
    (net (code "57") (name "12V_7") (class "Default")
      (node (ref "D24") (pin "1") (pinfunction "A_1") (pintype "passive"))
      (node (ref "D25") (pin "2") (pinfunction "K_2") (pintype "passive"))
      (node (ref "K6") (pin "4") (pinfunction "4_4") (pintype "passive"))
      (node (ref "P27") (pin "2") (pinfunction "2_2") (pintype "passive"))
      (node (ref "Q20") (pin "2") (pinfunction "E_2") (pintype "passive"))
      (node (ref "R77") (pin "2") (pinfunction "2_2") (pintype "passive"))
    )
    (net (code "58") (name "Net-(D7-K)") (class "Default")
      (node (ref "D7") (pin "2") (pinfunction "K_2") (pintype "passive"))
      (node (ref "R30") (pin "1") (pinfunction "1_1") (pintype "passive"))
    )
    (net (code "59") (name "Net-(D9-K)") (class "Default")
      (node (ref "D9") (pin "2") (pinfunction "K_2") (pintype "passive"))
      (node (ref "R31") (pin "1") (pinfunction "1_1") (pintype "passive"))
    )
    (net (code "60") (name "Net-(D11-A)") (class "Default")
      (node (ref "D11") (pin "2") (pinfunction "A_2") (pintype "passive"))
      (node (ref "K1") (pin "5") (pinfunction "5_5") (pintype "passive"))
      (node (ref "Q6") (pin "3") (pinfunction "C_3") (pintype "passive"))
    )
    (net (code "61") (name "Net-(D12-K)") (class "Default")
      (node (ref "D12") (pin "2") (pinfunction "K_2") (pintype "passive"))
      (node (ref "R41") (pin "1") (pinfunction "1_1") (pintype "passive"))
    )
    (net (code "62") (name "Net-(D14-K)") (class "Default")
      (node (ref "D14") (pin "2") (pinfunction "K_2") (pintype "passive"))
      (node (ref "R42") (pin "1") (pinfunction "1_1") (pintype "passive"))
    )
    (net (code "63") (name "Net-(D16-A)") (class "Default")
      (node (ref "D16") (pin "2") (pinfunction "A_2") (pintype "passive"))
      (node (ref "K2") (pin "5") (pinfunction "5_5") (pintype "passive"))
      (node (ref "Q11") (pin "3") (pinfunction "C_3") (pintype "passive"))
    )
    (net (code "64") (name "Net-(D17-K)") (class "Default")
      (node (ref "D17") (pin "2") (pinfunction "K_2") (pintype "passive"))
      (node (ref "R54") (pin "1") (pinfunction "1_1") (pintype "passive"))
    )
    (net (code "65") (name "Net-(D19-K)") (class "Default")
      (node (ref "D19") (pin "2") (pinfunction "K_2") (pintype "passive"))
      (node (ref "R55") (pin "1") (pinfunction "1_1") (pintype "passive"))
    )
    (net (code "66") (name "Net-(D21-A)") (class "Default")
      (node (ref "D21") (pin "2") (pinfunction "A_2") (pintype "passive"))
      (node (ref "K3") (pin "5") (pinfunction "5_5") (pintype "passive"))
      (node (ref "Q16") (pin "3") (pinfunction "C_3") (pintype "passive"))
    )
    (net (code "67") (name "Net-(D22-K)") (class "Default")
      (node (ref "D22") (pin "2") (pinfunction "K_2") (pintype "passive"))
      (node (ref "R67") (pin "1") (pinfunction "1_1") (pintype "passive"))
    )
    (net (code "68") (name "Net-(D24-K)") (class "Default")
      (node (ref "D24") (pin "2") (pinfunction "K_2") (pintype "passive"))
      (node (ref "R68") (pin "1") (pinfunction "1_1") (pintype "passive"))
    )
    (net (code "69") (name "Net-(D26-A)") (class "Default")
      (node (ref "D26") (pin "2") (pinfunction "A_2") (pintype "passive"))
      (node (ref "K4") (pin "5") (pinfunction "5_5") (pintype "passive"))
      (node (ref "Q21") (pin "3") (pinfunction "C_3") (pintype "passive"))
    )
    (net (code "70") (name "Net-(D27-A)") (class "Default")
      (node (ref "D27") (pin "2") (pinfunction "A_2") (pintype "passive"))
      (node (ref "K5") (pin "5") (pinfunction "5_5") (pintype "passive"))
      (node (ref "Q22") (pin "3") (pinfunction "C_3") (pintype "passive"))
    )
    (net (code "71") (name "Net-(D28-A)") (class "Default")
      (node (ref "D28") (pin "2") (pinfunction "A_2") (pintype "passive"))
      (node (ref "K6") (pin "5") (pinfunction "5_5") (pintype "passive"))
      (node (ref "Q23") (pin "3") (pinfunction "C_3") (pintype "passive"))
    )
    (net (code "72") (name "Net-(D29-A)") (class "Default")
      (node (ref "D29") (pin "2") (pinfunction "A_2") (pintype "passive"))
      (node (ref "K7") (pin "5") (pinfunction "5_5") (pintype "passive"))
      (node (ref "Q24") (pin "3") (pinfunction "C_3") (pintype "passive"))
    )
    (net (code "73") (name "Net-(D30-A)") (class "Default")
      (node (ref "D30") (pin "2") (pinfunction "A_2") (pintype "passive"))
      (node (ref "K8") (pin "5") (pinfunction "5_5") (pintype "passive"))
      (node (ref "Q25") (pin "3") (pinfunction "C_3") (pintype "passive"))
    )
    (net (code "74") (name "Net-(Q2-B)") (class "Default")
      (node (ref "Q2") (pin "1") (pinfunction "B_1") (pintype "passive"))
      (node (ref "R24") (pin "1") (pinfunction "1_1") (pintype "passive"))
      (node (ref "R25") (pin "2") (pinfunction "2_2") (pintype "passive"))
    )
    (net (code "75") (name "Net-(Q3-D)") (class "Default")
      (node (ref "F1") (pin "1") (pinfunction "1_1") (pintype "passive"))
      (node (ref "Q3") (pin "2") (pinfunction "D_2") (pintype "passive"))
      (node (ref "R30") (pin "2") (pinfunction "2_2") (pintype "passive"))
    )
    (net (code "76") (name "Net-(Q4-D)") (class "Default")
      (node (ref "F2") (pin "1") (pinfunction "1_1") (pintype "passive"))
      (node (ref "Q4") (pin "2") (pinfunction "D_2") (pintype "passive"))
      (node (ref "R31") (pin "2") (pinfunction "2_2") (pintype "passive"))
    )
    (net (code "77") (name "Net-(Q5-B)") (class "Default")
      (node (ref "Q5") (pin "1") (pinfunction "B_1") (pintype "passive"))
      (node (ref "R32") (pin "1") (pinfunction "1_1") (pintype "passive"))
      (node (ref "R33") (pin "2") (pinfunction "2_2") (pintype "passive"))
    )
    (net (code "78") (name "Net-(Q6-B)") (class "Default")
      (node (ref "Q6") (pin "1") (pinfunction "B_1") (pintype "passive"))
      (node (ref "R36") (pin "1") (pinfunction "1_1") (pintype "passive"))
    )
    (net (code "79") (name "Net-(Q7-B)") (class "Default")
      (node (ref "Q7") (pin "1") (pinfunction "B_1") (pintype "passive"))
      (node (ref "R39") (pin "1") (pinfunction "1_1") (pintype "passive"))
      (node (ref "R40") (pin "2") (pinfunction "2_2") (pintype "passive"))
    )
    (net (code "80") (name "Net-(Q8-D)") (class "Default")
      (node (ref "F3") (pin "1") (pinfunction "1_1") (pintype "passive"))
      (node (ref "Q8") (pin "2") (pinfunction "D_2") (pintype "passive"))
      (node (ref "R41") (pin "2") (pinfunction "2_2") (pintype "passive"))
    )
    (net (code "81") (name "Net-(Q9-D)") (class "Default")
      (node (ref "F4") (pin "1") (pinfunction "1_1") (pintype "passive"))
      (node (ref "Q9") (pin "2") (pinfunction "D_2") (pintype "passive"))
      (node (ref "R42") (pin "2") (pinfunction "2_2") (pintype "passive"))
    )
    (net (code "82") (name "Net-(Q10-B)") (class "Default")
      (node (ref "Q10") (pin "1") (pinfunction "B_1") (pintype "passive"))
      (node (ref "R47") (pin "1") (pinfunction "1_1") (pintype "passive"))
      (node (ref "R48") (pin "2") (pinfunction "2_2") (pintype "passive"))
    )
    (net (code "83") (name "Net-(Q11-B)") (class "Default")
      (node (ref "Q11") (pin "1") (pinfunction "B_1") (pintype "passive"))
      (node (ref "R51") (pin "1") (pinfunction "1_1") (pintype "passive"))
    )
    (net (code "84") (name "Net-(Q12-B)") (class "Default")
      (node (ref "Q12") (pin "1") (pinfunction "B_1") (pintype "passive"))
      (node (ref "R56") (pin "1") (pinfunction "1_1") (pintype "passive"))
      (node (ref "R57") (pin "2") (pinfunction "2_2") (pintype "passive"))
    )
    (net (code "85") (name "Net-(Q13-D)") (class "Default")
      (node (ref "F5") (pin "1") (pinfunction "1_1") (pintype "passive"))
      (node (ref "Q13") (pin "2") (pinfunction "D_2") (pintype "passive"))
      (node (ref "R54") (pin "2") (pinfunction "2_2") (pintype "passive"))
    )
    (net (code "86") (name "Net-(Q14-D)") (class "Default")
      (node (ref "F6") (pin "1") (pinfunction "1_1") (pintype "passive"))
      (node (ref "Q14") (pin "2") (pinfunction "D_2") (pintype "passive"))
      (node (ref "R55") (pin "2") (pinfunction "2_2") (pintype "passive"))
    )
    (net (code "87") (name "Net-(Q15-B)") (class "Default")
      (node (ref "Q15") (pin "1") (pinfunction "B_1") (pintype "passive"))
      (node (ref "R62") (pin "1") (pinfunction "1_1") (pintype "passive"))
      (node (ref "R63") (pin "2") (pinfunction "2_2") (pintype "passive"))
    )
    (net (code "88") (name "Net-(Q16-B)") (class "Default")
      (node (ref "Q16") (pin "1") (pinfunction "B_1") (pintype "passive"))
      (node (ref "R66") (pin "1") (pinfunction "1_1") (pintype "passive"))
    )
    (net (code "89") (name "Net-(Q17-D)") (class "Default")
      (node (ref "F7") (pin "1") (pinfunction "1_1") (pintype "passive"))
      (node (ref "Q17") (pin "2") (pinfunction "D_2") (pintype "passive"))
      (node (ref "R67") (pin "2") (pinfunction "2_2") (pintype "passive"))
    )
    (net (code "90") (name "Net-(Q18-D)") (class "Default")
      (node (ref "F8") (pin "1") (pinfunction "1_1") (pintype "passive"))
      (node (ref "Q18") (pin "2") (pinfunction "D_2") (pintype "passive"))
      (node (ref "R68") (pin "2") (pinfunction "2_2") (pintype "passive"))
    )
    (net (code "91") (name "Net-(Q19-B)") (class "Default")
      (node (ref "Q19") (pin "1") (pinfunction "B_1") (pintype "passive"))
      (node (ref "R71") (pin "1") (pinfunction "1_1") (pintype "passive"))
      (node (ref "R72") (pin "2") (pinfunction "2_2") (pintype "passive"))
    )
    (net (code "92") (name "Net-(Q20-B)") (class "Default")
      (node (ref "Q20") (pin "1") (pinfunction "B_1") (pintype "passive"))
      (node (ref "R77") (pin "1") (pinfunction "1_1") (pintype "passive"))
      (node (ref "R78") (pin "2") (pinfunction "2_2") (pintype "passive"))
    )
    (net (code "93") (name "Net-(Q21-B)") (class "Default")
      (node (ref "Q21") (pin "1") (pinfunction "B_1") (pintype "passive"))
      (node (ref "R81") (pin "1") (pinfunction "1_1") (pintype "passive"))
    )
    (net (code "94") (name "Net-(Q22-B)") (class "Default")
      (node (ref "Q22") (pin "1") (pinfunction "B_1") (pintype "passive"))
      (node (ref "R84") (pin "1") (pinfunction "1_1") (pintype "passive"))
    )
    (net (code "95") (name "Net-(Q23-B)") (class "Default")
      (node (ref "Q23") (pin "1") (pinfunction "B_1") (pintype "passive"))
      (node (ref "R85") (pin "1") (pinfunction "1_1") (pintype "passive"))
    )
    (net (code "96") (name "Net-(Q24-B)") (class "Default")
      (node (ref "Q24") (pin "1") (pinfunction "B_1") (pintype "passive"))
      (node (ref "R86") (pin "1") (pinfunction "1_1") (pintype "passive"))
    )
    (net (code "97") (name "Net-(Q25-B)") (class "Default")
      (node (ref "Q25") (pin "1") (pinfunction "B_1") (pintype "passive"))
      (node (ref "R87") (pin "1") (pinfunction "1_1") (pintype "passive"))
    )
    (net (code "98") (name "VSS") (class "Default")
      (node (ref "P14") (pin "1") (pinfunction "1_1") (pintype "passive"))
      (node (ref "P16") (pin "1") (pinfunction "1_1") (pintype "passive"))
      (node (ref "P18") (pin "1") (pinfunction "1_1") (pintype "passive"))
      (node (ref "P20") (pin "1") (pinfunction "1_1") (pintype "passive"))
      (node (ref "P22") (pin "1") (pinfunction "1_1") (pintype "passive"))
      (node (ref "P24") (pin "1") (pinfunction "1_1") (pintype "passive"))
      (node (ref "P26") (pin "1") (pinfunction "1_1") (pintype "passive"))
      (node (ref "P28") (pin "1") (pinfunction "1_1") (pintype "passive"))
      (node (ref "Q11") (pin "2") (pinfunction "E_2") (pintype "passive"))
      (node (ref "Q13") (pin "3") (pinfunction "S_3") (pintype "passive"))
      (node (ref "Q14") (pin "3") (pinfunction "S_3") (pintype "passive"))
      (node (ref "Q16") (pin "2") (pinfunction "E_2") (pintype "passive"))
      (node (ref "Q17") (pin "3") (pinfunction "S_3") (pintype "passive"))
      (node (ref "Q18") (pin "3") (pinfunction "S_3") (pintype "passive"))
      (node (ref "Q21") (pin "2") (pinfunction "E_2") (pintype "passive"))
      (node (ref "Q22") (pin "2") (pinfunction "E_2") (pintype "passive"))
      (node (ref "Q23") (pin "2") (pinfunction "E_2") (pintype "passive"))
      (node (ref "Q24") (pin "2") (pinfunction "E_2") (pintype "passive"))
      (node (ref "Q25") (pin "2") (pinfunction "E_2") (pintype "passive"))
      (node (ref "Q3") (pin "3") (pinfunction "S_3") (pintype "passive"))
      (node (ref "Q4") (pin "3") (pinfunction "S_3") (pintype "passive"))
      (node (ref "Q6") (pin "2") (pinfunction "E_2") (pintype "passive"))
      (node (ref "Q8") (pin "3") (pinfunction "S_3") (pintype "passive"))
      (node (ref "Q9") (pin "3") (pinfunction "S_3") (pintype "passive"))
      (node (ref "R28") (pin "1") (pinfunction "1_1") (pintype "passive"))
      (node (ref "R29") (pin "1") (pinfunction "1_1") (pintype "passive"))
      (node (ref "R37") (pin "1") (pinfunction "1_1") (pintype "passive"))
      (node (ref "R38") (pin "1") (pinfunction "1_1") (pintype "passive"))
      (node (ref "R45") (pin "1") (pinfunction "1_1") (pintype "passive"))
      (node (ref "R46") (pin "1") (pinfunction "1_1") (pintype "passive"))
      (node (ref "R52") (pin "1") (pinfunction "1_1") (pintype "passive"))
      (node (ref "R53") (pin "1") (pinfunction "1_1") (pintype "passive"))
      (node (ref "R60") (pin "1") (pinfunction "1_1") (pintype "passive"))
      (node (ref "R61") (pin "1") (pinfunction "1_1") (pintype "passive"))
      (node (ref "R69") (pin "1") (pinfunction "1_1") (pintype "passive"))
      (node (ref "R70") (pin "1") (pinfunction "1_1") (pintype "passive"))
      (node (ref "R75") (pin "1") (pinfunction "1_1") (pintype "passive"))
      (node (ref "R76") (pin "1") (pinfunction "1_1") (pintype "passive"))
      (node (ref "R82") (pin "1") (pinfunction "1_1") (pintype "passive"))
      (node (ref "R83") (pin "1") (pinfunction "1_1") (pintype "passive"))
    )
    (net (code "99") (name "unconnected-(K1-Pad3)") (class "Default")
      (node (ref "K1") (pin "3") (pinfunction "3_3") (pintype "passive"))
    )
    (net (code "100") (name "unconnected-(K2-Pad3)") (class "Default")
      (node (ref "K2") (pin "3") (pinfunction "3_3") (pintype "passive"))
    )
    (net (code "101") (name "unconnected-(K3-Pad3)") (class "Default")
      (node (ref "K3") (pin "3") (pinfunction "3_3") (pintype "passive"))
    )
    (net (code "102") (name "unconnected-(K4-Pad3)") (class "Default")
      (node (ref "K4") (pin "3") (pinfunction "3_3") (pintype "passive"))
    )
    (net (code "103") (name "unconnected-(K5-Pad3)") (class "Default")
      (node (ref "K5") (pin "3") (pinfunction "3_3") (pintype "passive"))
    )
    (net (code "104") (name "unconnected-(K6-Pad3)") (class "Default")
      (node (ref "K6") (pin "3") (pinfunction "3_3") (pintype "passive"))
    )
    (net (code "105") (name "unconnected-(K7-Pad3)") (class "Default")
      (node (ref "K7") (pin "3") (pinfunction "3_3") (pintype "passive"))
    )
    (net (code "106") (name "unconnected-(K8-Pad3)") (class "Default")
      (node (ref "K8") (pin "3") (pinfunction "3_3") (pintype "passive"))
    )
  )
)
